# CD_brains.net
KiCad netlist of a schematic drawn in EAGLE
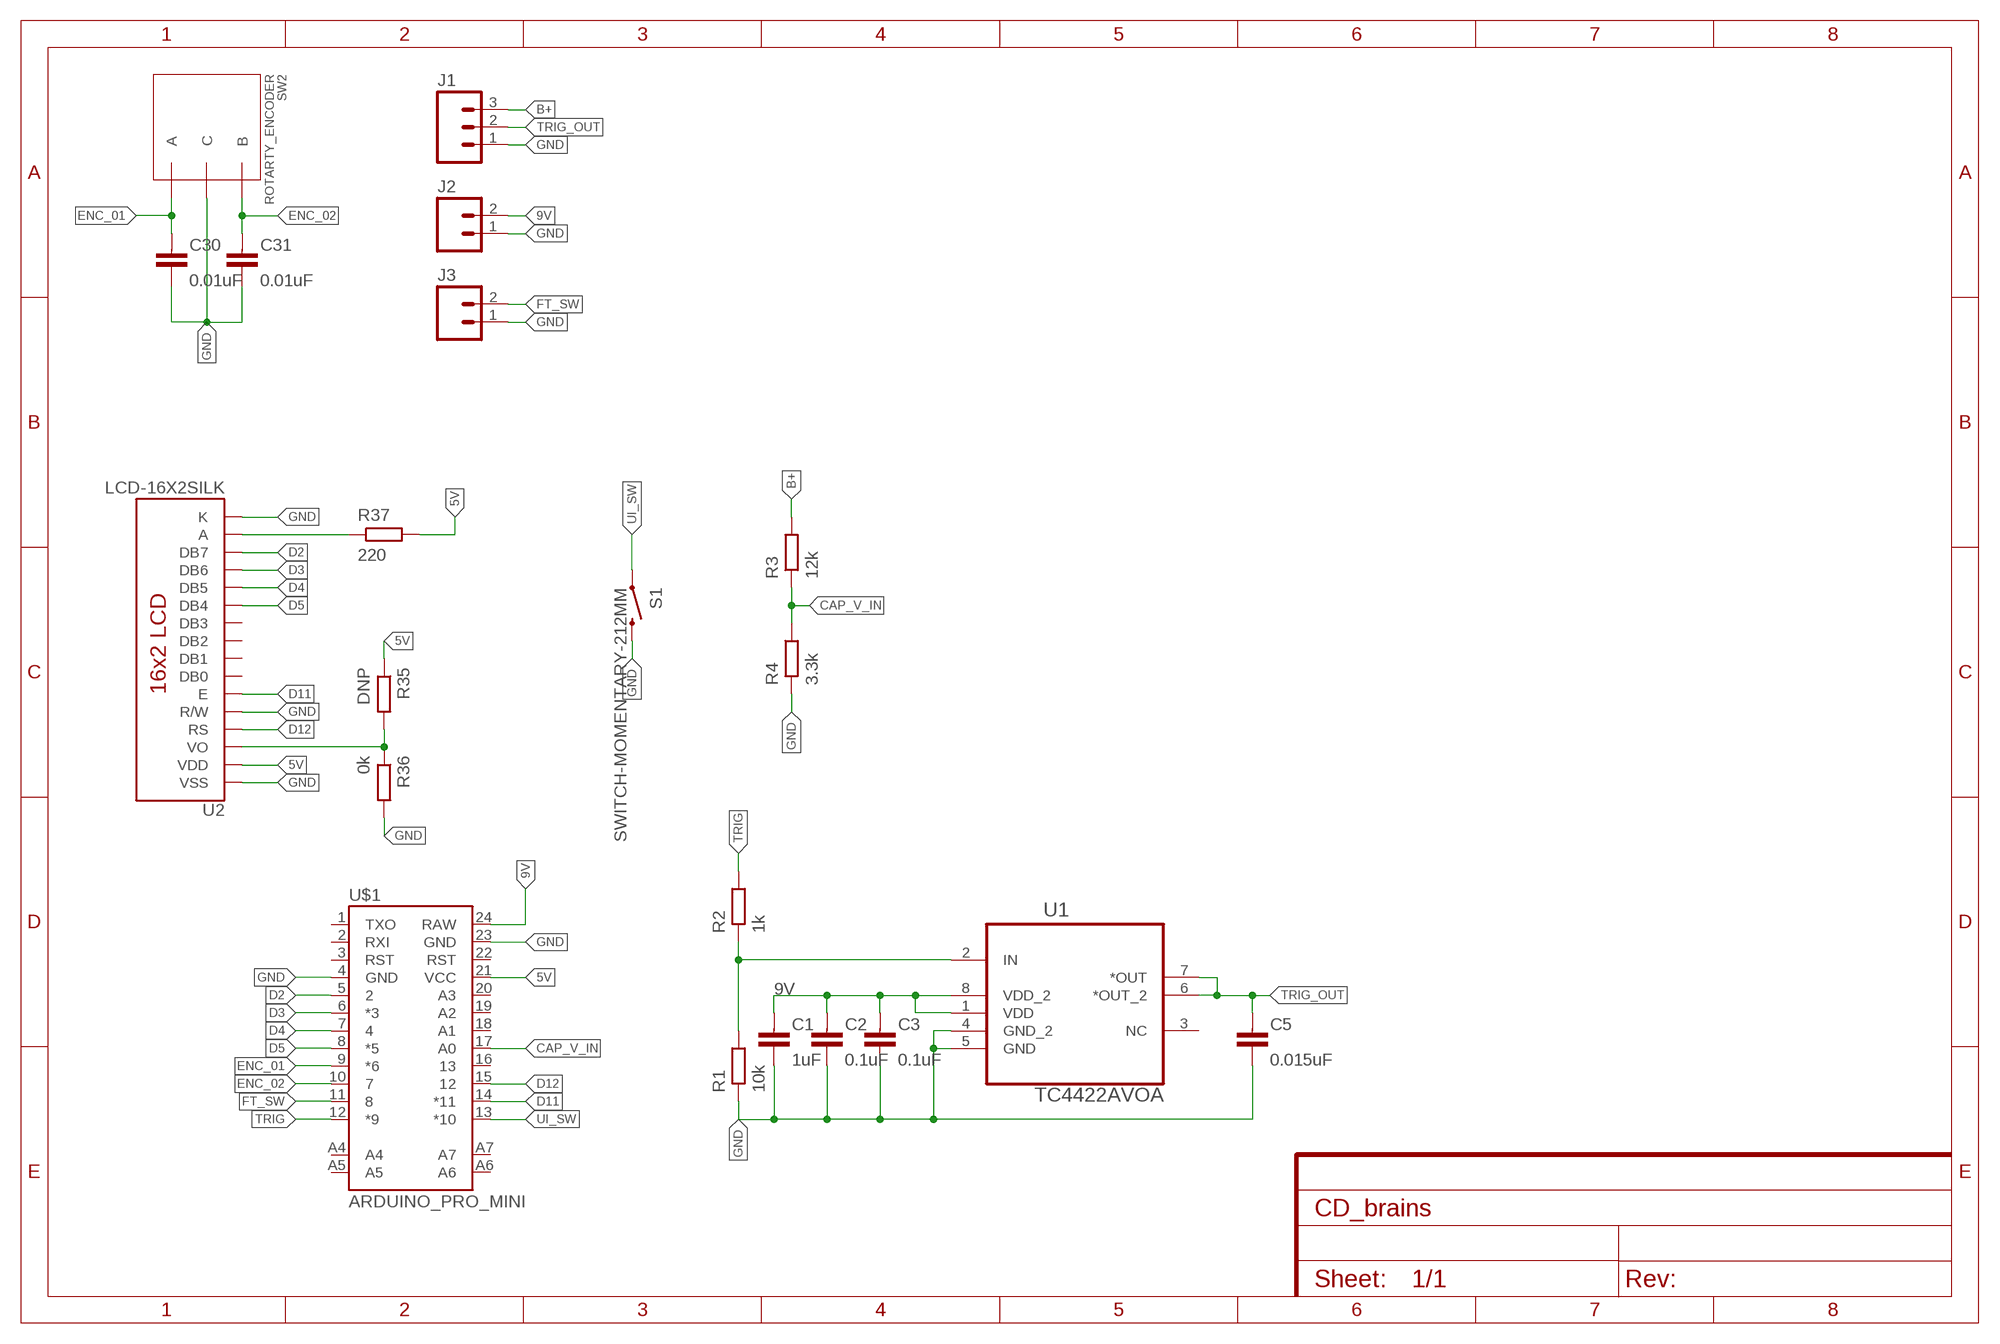
[diagram p0: schematic, sheet 1]

(export (version "E")
  (design (tool "Eeschema 10.0.6"))
  (components
    (comp (ref "C1")
      (value "1uF")
      (footprint "eagle-import:C0805-N")
      (libsource (lib "eagle-import") (part "CAPACITOR0805-N"))
    )
    (comp (ref "C2")
      (value "0.1uF")
      (footprint "eagle-import:C0603-N")
      (libsource (lib "eagle-import") (part "CAPACITOR0603-N"))
    )
    (comp (ref "C3")
      (value "0.1uF")
      (footprint "eagle-import:C0603-N")
      (libsource (lib "eagle-import") (part "CAPACITOR0603-N"))
    )
    (comp (ref "C5")
      (value "0.015uF")
      (footprint "eagle-import:C0603-N")
      (libsource (lib "eagle-import") (part "CAPACITOR0603-N"))
    )
    (comp (ref "C30")
      (value "0.01uF")
      (footprint "eagle-import:C0603-N")
      (libsource (lib "eagle-import") (part "CAPACITOR0603-N"))
    )
    (comp (ref "C31")
      (value "0.01uF")
      (footprint "eagle-import:C0603-N")
      (libsource (lib "eagle-import") (part "CAPACITOR0603-N"))
    )
    (comp (ref "J1")
      (value "M03LOCK_NO_SILK")
      (footprint "eagle-import:1X03_LOCK_NO_SILK")
      (libsource (lib "eagle-import") (part "M03LOCK_NO_SILK"))
    )
    (comp (ref "J2")
      (value "M02LOCK")
      (footprint "eagle-import:1X02_LOCK")
      (libsource (lib "eagle-import") (part "M02LOCK"))
    )
    (comp (ref "J3")
      (value "M02LOCK")
      (footprint "eagle-import:1X02_LOCK")
      (libsource (lib "eagle-import") (part "M02LOCK"))
    )
    (comp (ref "R1")
      (value "10k")
      (footprint "eagle-import:R0603-N")
      (libsource (lib "eagle-import") (part "RESISTOR0603-N"))
    )
    (comp (ref "R2")
      (value "1k")
      (footprint "eagle-import:R0603-N")
      (libsource (lib "eagle-import") (part "RESISTOR0603-N"))
    )
    (comp (ref "R3")
      (value "12k")
      (footprint "eagle-import:R0603-N")
      (libsource (lib "eagle-import") (part "RESISTOR0603-N"))
    )
    (comp (ref "R4")
      (value "3.3k")
      (footprint "eagle-import:R0603-N")
      (libsource (lib "eagle-import") (part "RESISTOR0603-N"))
    )
    (comp (ref "R35")
      (value "DNP")
      (footprint "eagle-import:R0603-N")
      (libsource (lib "eagle-import") (part "RESISTOR0603-N"))
    )
    (comp (ref "R36")
      (value "0k")
      (footprint "eagle-import:R0603-N")
      (libsource (lib "eagle-import") (part "RESISTOR0603-N"))
    )
    (comp (ref "R37")
      (value "220")
      (footprint "eagle-import:R0603-N")
      (libsource (lib "eagle-import") (part "RESISTOR0603-N"))
    )
    (comp (ref "S1")
      (value "SWITCH-MOMENTARY-212MM")
      (footprint "eagle-import:TACTILE-PTH-12MM")
      (libsource (lib "eagle-import") (part "SWITCH-MOMENTARY-212MM"))
    )
    (comp (ref "SW2")
      (value "ROTARTY_ENCODER")
      (footprint "eagle-import:ROTARY_ENC_PLAIN")
      (libsource (lib "eagle-import") (part "ROTARTY_ENCODER"))
    )
    (comp (ref "U$1")
      (value "ARDUINO_PRO_MINI")
      (footprint "eagle-import:ARDUINO_PRO_MINI")
      (libsource (lib "eagle-import") (part "ARDUINO_PRO_MINI"))
    )
    (comp (ref "U1")
      (value "TC4422AVOA")
      (footprint "eagle-import:SOIC127P600X175-8N")
      (libsource (lib "eagle-import") (part "TC4422AVOA"))
    )
    (comp (ref "U2")
      (value "LCD-16X2SILK")
      (footprint "eagle-import:LCD-16X2")
      (libsource (lib "eagle-import") (part "LCD-16X2SILK"))
    )
  )
  (nets
    (net (code "1") (name "5V") (class "Default")
      (node (ref "R35") (pin "1") (pinfunction "P$1_1") (pintype "passive"))
      (node (ref "R37") (pin "2") (pinfunction "P$2_2") (pintype "passive"))
      (node (ref "U$1") (pin "21") (pinfunction "VCC_21") (pintype "bidirectional"))
      (node (ref "U2") (pin "2") (pinfunction "VDD_2") (pintype "power_in"))
    )
    (net (code "2") (name "9V") (class "Default")
      (node (ref "C1") (pin "1") (pinfunction "1_1") (pintype "passive"))
      (node (ref "C2") (pin "1") (pinfunction "1_1") (pintype "passive"))
      (node (ref "C3") (pin "1") (pinfunction "1_1") (pintype "passive"))
      (node (ref "J2") (pin "2") (pinfunction "2_2") (pintype "passive"))
      (node (ref "U$1") (pin "24") (pinfunction "RAW_24") (pintype "bidirectional"))
      (node (ref "U1") (pin "1") (pinfunction "VDD_1") (pintype "power_in"))
      (node (ref "U1") (pin "8") (pinfunction "VDD_2_8") (pintype "power_in"))
    )
    (net (code "3") (name "B+") (class "Default")
      (node (ref "J1") (pin "3") (pinfunction "3_3") (pintype "passive"))
      (node (ref "R3") (pin "2") (pinfunction "P$2_2") (pintype "passive"))
    )
    (net (code "4") (name "CAP_V_IN") (class "Default")
      (node (ref "R3") (pin "1") (pinfunction "P$1_1") (pintype "passive"))
      (node (ref "R4") (pin "2") (pinfunction "P$2_2") (pintype "passive"))
      (node (ref "U$1") (pin "17") (pinfunction "A0_17") (pintype "bidirectional"))
    )
    (net (code "5") (name "D2") (class "Default")
      (node (ref "U$1") (pin "5") (pinfunction "2_5") (pintype "bidirectional"))
      (node (ref "U2") (pin "14") (pinfunction "DB7_14") (pintype "bidirectional"))
    )
    (net (code "6") (name "D3") (class "Default")
      (node (ref "U$1") (pin "6") (pinfunction "*3_6") (pintype "bidirectional"))
      (node (ref "U2") (pin "13") (pinfunction "DB6_13") (pintype "bidirectional"))
    )
    (net (code "7") (name "D4") (class "Default")
      (node (ref "U$1") (pin "7") (pinfunction "4_7") (pintype "bidirectional"))
      (node (ref "U2") (pin "12") (pinfunction "DB5_12") (pintype "bidirectional"))
    )
    (net (code "8") (name "D5") (class "Default")
      (node (ref "U$1") (pin "8") (pinfunction "*5_8") (pintype "bidirectional"))
      (node (ref "U2") (pin "11") (pinfunction "DB4_11") (pintype "bidirectional"))
    )
    (net (code "9") (name "D11") (class "Default")
      (node (ref "U$1") (pin "14") (pinfunction "*11_14") (pintype "bidirectional"))
      (node (ref "U2") (pin "6") (pinfunction "E_6") (pintype "input"))
    )
    (net (code "10") (name "D12") (class "Default")
      (node (ref "U$1") (pin "15") (pinfunction "12_15") (pintype "bidirectional"))
      (node (ref "U2") (pin "4") (pinfunction "RS_4") (pintype "input"))
    )
    (net (code "11") (name "ENC_01") (class "Default")
      (node (ref "C30") (pin "1") (pinfunction "1_1") (pintype "passive"))
      (node (ref "SW2") (pin "A") (pinfunction "A_A") (pintype "bidirectional"))
      (node (ref "U$1") (pin "9") (pinfunction "*6_9") (pintype "bidirectional"))
    )
    (net (code "12") (name "ENC_02") (class "Default")
      (node (ref "C31") (pin "1") (pinfunction "1_1") (pintype "passive"))
      (node (ref "SW2") (pin "B") (pinfunction "B_B") (pintype "bidirectional"))
      (node (ref "U$1") (pin "10") (pinfunction "7_10") (pintype "bidirectional"))
    )
    (net (code "13") (name "FT_SW") (class "Default")
      (node (ref "J3") (pin "2") (pinfunction "2_2") (pintype "passive"))
      (node (ref "U$1") (pin "11") (pinfunction "8_11") (pintype "bidirectional"))
    )
    (net (code "14") (name "GND") (class "Default")
      (node (ref "C1") (pin "2") (pinfunction "2_2") (pintype "passive"))
      (node (ref "C2") (pin "2") (pinfunction "2_2") (pintype "passive"))
      (node (ref "C3") (pin "2") (pinfunction "2_2") (pintype "passive"))
      (node (ref "C30") (pin "2") (pinfunction "2_2") (pintype "passive"))
      (node (ref "C31") (pin "2") (pinfunction "2_2") (pintype "passive"))
      (node (ref "C5") (pin "2") (pinfunction "2_2") (pintype "passive"))
      (node (ref "J1") (pin "1") (pinfunction "1_1") (pintype "passive"))
      (node (ref "J2") (pin "1") (pinfunction "1_1") (pintype "passive"))
      (node (ref "J3") (pin "1") (pinfunction "1_1") (pintype "passive"))
      (node (ref "R1") (pin "1") (pinfunction "P$1_1") (pintype "passive"))
      (node (ref "R36") (pin "2") (pinfunction "P$2_2") (pintype "passive"))
      (node (ref "R4") (pin "1") (pinfunction "P$1_1") (pintype "passive"))
      (node (ref "S1") (pin "3") (pinfunction "2_3") (pintype "passive"))
      (node (ref "SW2") (pin "C") (pinfunction "C_C") (pintype "bidirectional"))
      (node (ref "U$1") (pin "23") (pinfunction "GND_23") (pintype "bidirectional"))
      (node (ref "U$1") (pin "4") (pinfunction "GND_4") (pintype "bidirectional"))
      (node (ref "U1") (pin "4") (pinfunction "GND_2_4") (pintype "passive"))
      (node (ref "U1") (pin "5") (pinfunction "GND_5") (pintype "passive"))
      (node (ref "U2") (pin "1") (pinfunction "VSS_1") (pintype "power_in"))
      (node (ref "U2") (pin "16") (pinfunction "K_16") (pintype "power_in"))
      (node (ref "U2") (pin "5") (pinfunction "R/W_5") (pintype "input"))
    )
    (net (code "15") (name "Net-(R1-P$2)") (class "Default")
      (node (ref "R1") (pin "2") (pinfunction "P$2_2") (pintype "passive"))
      (node (ref "R2") (pin "1") (pinfunction "P$1_1") (pintype "passive"))
      (node (ref "U1") (pin "2") (pinfunction "IN_2") (pintype "input"))
    )
    (net (code "16") (name "Net-(R35-P$2)") (class "Default")
      (node (ref "R35") (pin "2") (pinfunction "P$2_2") (pintype "passive"))
      (node (ref "R36") (pin "1") (pinfunction "P$1_1") (pintype "passive"))
      (node (ref "U2") (pin "3") (pinfunction "VO_3") (pintype "bidirectional"))
    )
    (net (code "17") (name "Net-(R37-P$1)") (class "Default")
      (node (ref "R37") (pin "1") (pinfunction "P$1_1") (pintype "passive"))
      (node (ref "U2") (pin "15") (pinfunction "A_15") (pintype "power_in"))
    )
    (net (code "18") (name "TRIG") (class "Default")
      (node (ref "R2") (pin "2") (pinfunction "P$2_2") (pintype "passive"))
      (node (ref "U$1") (pin "12") (pinfunction "*9_12") (pintype "bidirectional"))
    )
    (net (code "19") (name "TRIG_OUT") (class "Default")
      (node (ref "C5") (pin "1") (pinfunction "1_1") (pintype "passive"))
      (node (ref "J1") (pin "2") (pinfunction "2_2") (pintype "passive"))
      (node (ref "U1") (pin "6") (pinfunction "*OUT_2_6") (pintype "output"))
      (node (ref "U1") (pin "7") (pinfunction "*OUT_7") (pintype "output"))
    )
    (net (code "20") (name "UI_SW") (class "Default")
      (node (ref "S1") (pin "1") (pinfunction "1_1") (pintype "passive"))
      (node (ref "U$1") (pin "13") (pinfunction "*10_13") (pintype "bidirectional"))
    )
    (net (code "21") (name "unconnected-(U$1-13-Pad16)") (class "Default")
      (node (ref "U$1") (pin "16") (pinfunction "13_16") (pintype "bidirectional"))
    )
    (net (code "22") (name "unconnected-(U$1-A1-Pad18)") (class "Default")
      (node (ref "U$1") (pin "18") (pinfunction "A1_18") (pintype "bidirectional"))
    )
    (net (code "23") (name "unconnected-(U$1-A2-Pad19)") (class "Default")
      (node (ref "U$1") (pin "19") (pinfunction "A2_19") (pintype "bidirectional"))
    )
    (net (code "24") (name "unconnected-(U$1-A3-Pad20)") (class "Default")
      (node (ref "U$1") (pin "20") (pinfunction "A3_20") (pintype "bidirectional"))
    )
    (net (code "25") (name "unconnected-(U$1-PadA4)") (class "Default")
      (node (ref "U$1") (pin "A4") (pinfunction "A4_A4") (pintype "bidirectional"))
    )
    (net (code "26") (name "unconnected-(U$1-PadA5)") (class "Default")
      (node (ref "U$1") (pin "A5") (pinfunction "A5_A5") (pintype "bidirectional"))
    )
    (net (code "27") (name "unconnected-(U$1-PadA6)") (class "Default")
      (node (ref "U$1") (pin "A6") (pinfunction "A6_A6") (pintype "bidirectional"))
    )
    (net (code "28") (name "unconnected-(U$1-PadA7)") (class "Default")
      (node (ref "U$1") (pin "A7") (pinfunction "A7_A7") (pintype "bidirectional"))
    )
    (net (code "29") (name "unconnected-(U$1-RST-Pad3)") (class "Default")
      (node (ref "U$1") (pin "3") (pinfunction "RST_3") (pintype "bidirectional"))
    )
    (net (code "30") (name "unconnected-(U$1-RST-Pad22)") (class "Default")
      (node (ref "U$1") (pin "22") (pinfunction "RST_22") (pintype "bidirectional"))
    )
    (net (code "31") (name "unconnected-(U$1-RXI-Pad2)") (class "Default")
      (node (ref "U$1") (pin "2") (pinfunction "RXI_2") (pintype "bidirectional"))
    )
    (net (code "32") (name "unconnected-(U$1-TXO-Pad1)") (class "Default")
      (node (ref "U$1") (pin "1") (pinfunction "TXO_1") (pintype "bidirectional"))
    )
    (net (code "33") (name "unconnected-(U1-NC-Pad3)") (class "Default")
      (node (ref "U1") (pin "3") (pinfunction "NC_3") (pintype "no_connect"))
    )
    (net (code "34") (name "unconnected-(U2-DB0-Pad7)") (class "Default")
      (node (ref "U2") (pin "7") (pinfunction "DB0_7") (pintype "bidirectional"))
    )
    (net (code "35") (name "unconnected-(U2-DB1-Pad8)") (class "Default")
      (node (ref "U2") (pin "8") (pinfunction "DB1_8") (pintype "bidirectional"))
    )
    (net (code "36") (name "unconnected-(U2-DB2-Pad9)") (class "Default")
      (node (ref "U2") (pin "9") (pinfunction "DB2_9") (pintype "bidirectional"))
    )
    (net (code "37") (name "unconnected-(U2-DB3-Pad10)") (class "Default")
      (node (ref "U2") (pin "10") (pinfunction "DB3_10") (pintype "bidirectional"))
    )
  )
)
